# ESP8266.net
KiCad netlist of a schematic drawn in Altium Designer
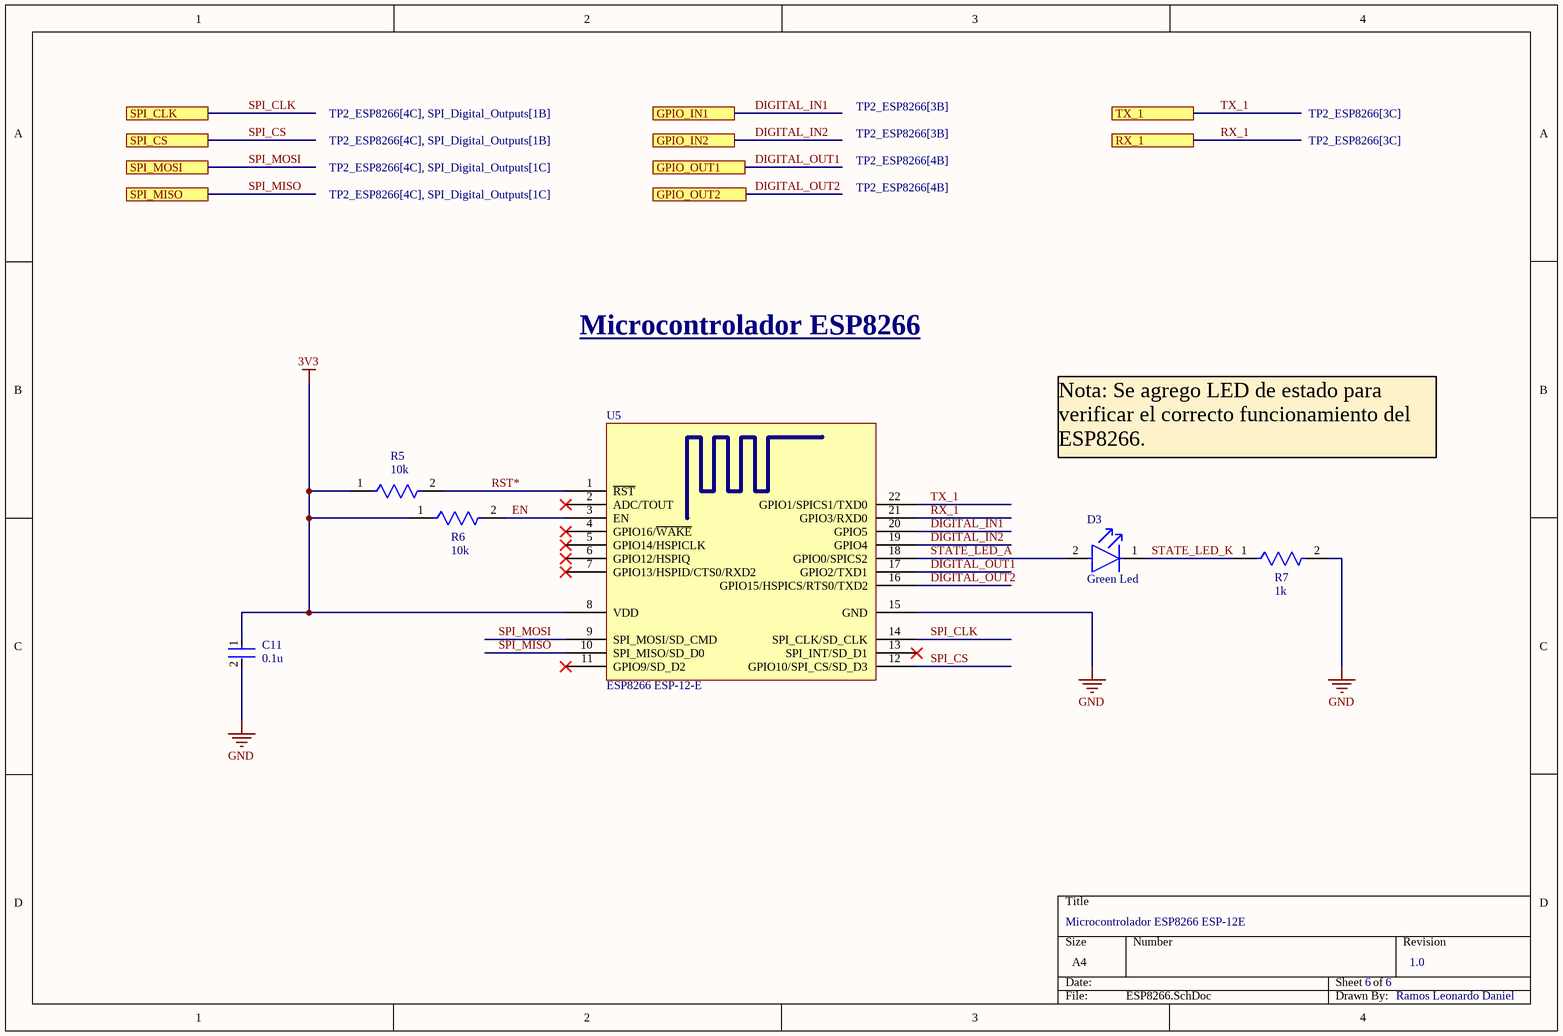
[diagram p0: ESP8266.SchDoc]

(export (version "E")
  (design (tool "Eeschema 10.0.6"))
  (components
    (comp (ref "C11")
      (value "0.1u")
      (footprint "FP-CC0805-0_85-MFG")
      (description "CAP CER 0.1UF 25V X7R 0805")
      (fields (field (name "MANUFACTURER PART NUMBER") "CC0805KRX7R8BB104") (field (name "TOLERANCE") "0.1"))
      (libsource (lib "Altium Content Vault") (part "11868f565c42a9108669ba33697ecf6"))
    )
    (comp (ref "D3")
      (value "Green Led")
      (footprint "FP-LTST-C190GKT-MFG")
      (description "LED GREEN CLEAR CHIP SMD LTST-C190GKT")
      (fields (field (name "VOLTAGE") "2V"))
      (libsource (lib "Altium Content Vault") (part "8706943c75ba83719d021d2fdc84c58"))
    )
    (comp (ref "R5")
      (value "CRCW08054K70JNEA")
      (footprint "FP-CRCW0805-e3-IPC_B")
      (description "RES Thick Film, 4.7kΩ, 5%, 0.125W, 200ppm/°C, 0805")
      (fields (field (name "TOLERANCE") "5%") (field (name "RESISTANCE") "10k"))
      (libsource (lib "Altium Content Vault") (part "1029c3af85768c4190bb7ad29bc67b5"))
    )
    (comp (ref "R6")
      (value "CRCW08054K70JNEA")
      (footprint "FP-CRCW0805-e3-IPC_B")
      (description "RES Thick Film, 4.7kΩ, 5%, 0.125W, 200ppm/°C, 0805")
      (fields (field (name "TOLERANCE") "5%") (field (name "RESISTANCE") "10k"))
      (libsource (lib "Altium Content Vault") (part "1029c3af85768c4190bb7ad29bc67b5"))
    )
    (comp (ref "R7")
      (value "CRCW08054K70JNEA")
      (footprint "FP-CRCW0805-e3-IPC_B")
      (description "RES Thick Film, 4.7kΩ, 5%, 0.125W, 200ppm/°C, 0805")
      (fields (field (name "TOLERANCE") "5%") (field (name "RESISTANCE") "1k"))
      (libsource (lib "Altium Content Vault") (part "1029c3af85768c4190bb7ad29bc67b5"))
    )
    (comp (ref "U5")
      (value "ESP8266 ESP-12-E")
      (footprint "ESP8266 ESP-12-E")
      (libsource (lib "ESP8266") (part "ESP8266 ESP-12-E"))
    )
  )
  (nets
    (net (code "1") (name "/DIGITAL_IN1") (class "Default")
      (node (ref "U5") (pin "20") (pinfunction "GPIO5_20") (pintype "passive"))
    )
    (net (code "2") (name "/DIGITAL_IN2") (class "Default")
      (node (ref "U5") (pin "19") (pinfunction "GPIO4_19") (pintype "passive"))
    )
    (net (code "3") (name "/DIGITAL_OUT1") (class "Default")
      (node (ref "U5") (pin "17") (pinfunction "GPIO2/TXD1_17") (pintype "passive"))
    )
    (net (code "4") (name "/DIGITAL_OUT2") (class "Default")
      (node (ref "U5") (pin "16") (pinfunction "GPIO15/HSPICS/RTS0/TXD2_16") (pintype "passive"))
    )
    (net (code "5") (name "/EN") (class "Default")
      (node (ref "R6") (pin "2") (pinfunction "2_2") (pintype "passive"))
      (node (ref "U5") (pin "3") (pinfunction "EN_3") (pintype "passive"))
    )
    (net (code "6") (name "/RST*") (class "Default")
      (node (ref "R5") (pin "2") (pinfunction "2_2") (pintype "passive"))
      (node (ref "U5") (pin "1") (pinfunction "~{RST}_1") (pintype "passive"))
    )
    (net (code "7") (name "/RX_1") (class "Default")
      (node (ref "U5") (pin "21") (pinfunction "GPIO3/RXD0_21") (pintype "passive"))
    )
    (net (code "8") (name "/SPI_CLK") (class "Default")
      (node (ref "U5") (pin "14") (pinfunction "SPI_CLK/SD_CLK_14") (pintype "passive"))
    )
    (net (code "9") (name "/SPI_CS") (class "Default")
      (node (ref "U5") (pin "12") (pinfunction "GPIO10/SPI_CS/SD_D3_12") (pintype "passive"))
    )
    (net (code "10") (name "/SPI_MISO") (class "Default")
      (node (ref "U5") (pin "10") (pinfunction "SPI_MISO/SD_D0_10") (pintype "passive"))
    )
    (net (code "11") (name "/SPI_MOSI") (class "Default")
      (node (ref "U5") (pin "9") (pinfunction "SPI_MOSI/SD_CMD_9") (pintype "passive"))
    )
    (net (code "12") (name "/STATE_LED_A") (class "Default")
      (node (ref "D3") (pin "2") (pinfunction "A_2") (pintype "passive"))
      (node (ref "U5") (pin "18") (pinfunction "GPIO0/SPICS2_18") (pintype "passive"))
    )
    (net (code "13") (name "/STATE_LED_K") (class "Default")
      (node (ref "D3") (pin "1") (pinfunction "C_1") (pintype "passive"))
      (node (ref "R7") (pin "1") (pinfunction "1_1") (pintype "passive"))
    )
    (net (code "14") (name "/TX_1") (class "Default")
      (node (ref "U5") (pin "22") (pinfunction "GPIO1/SPICS1/TXD0_22") (pintype "passive"))
    )
    (net (code "15") (name "3V3") (class "Default")
      (node (ref "C11") (pin "1") (pinfunction "1_1") (pintype "passive"))
      (node (ref "R5") (pin "1") (pinfunction "1_1") (pintype "passive"))
      (node (ref "R6") (pin "1") (pinfunction "1_1") (pintype "passive"))
      (node (ref "U5") (pin "8") (pinfunction "VDD_8") (pintype "passive"))
    )
    (net (code "16") (name "GND") (class "Default")
      (node (ref "C11") (pin "2") (pinfunction "2_2") (pintype "passive"))
      (node (ref "R7") (pin "2") (pinfunction "2_2") (pintype "passive"))
      (node (ref "U5") (pin "15") (pinfunction "GND_15") (pintype "passive"))
    )
    (net (code "17") (name "unconnected-(U5-ADC{slash}TOUT-Pad2)") (class "Default")
      (node (ref "U5") (pin "2") (pinfunction "ADC/TOUT_2") (pintype "passive+no_connect"))
    )
    (net (code "18") (name "unconnected-(U5-GPIO9{slash}SD_D2-Pad11)") (class "Default")
      (node (ref "U5") (pin "11") (pinfunction "GPIO9/SD_D2_11") (pintype "passive+no_connect"))
    )
    (net (code "19") (name "unconnected-(U5-GPIO12{slash}HSPIQ-Pad6)") (class "Default")
      (node (ref "U5") (pin "6") (pinfunction "GPIO12/HSPIQ_6") (pintype "passive+no_connect"))
    )
    (net (code "20") (name "unconnected-(U5-GPIO13{slash}HSPID{slash}CTS0{slash}RXD2-Pad7)") (class "Default")
      (node (ref "U5") (pin "7") (pinfunction "GPIO13/HSPID/CTS0/RXD2_7") (pintype "passive+no_connect"))
    )
    (net (code "21") (name "unconnected-(U5-GPIO14{slash}HSPICLK-Pad5)") (class "Default")
      (node (ref "U5") (pin "5") (pinfunction "GPIO14/HSPICLK_5") (pintype "passive+no_connect"))
    )
    (net (code "22") (name "unconnected-(U5-GPIO16{slash}~{WAKE}-Pad4)") (class "Default")
      (node (ref "U5") (pin "4") (pinfunction "GPIO16/~{WAKE}_4") (pintype "passive+no_connect"))
    )
    (net (code "23") (name "unconnected-(U5-SPI_INT{slash}SD_D1-Pad13)") (class "Default")
      (node (ref "U5") (pin "13") (pinfunction "SPI_INT/SD_D1_13") (pintype "passive+no_connect"))
    )
  )
)
